# Ultravolt_Board.net
KiCad netlist of a schematic drawn in EAGLE
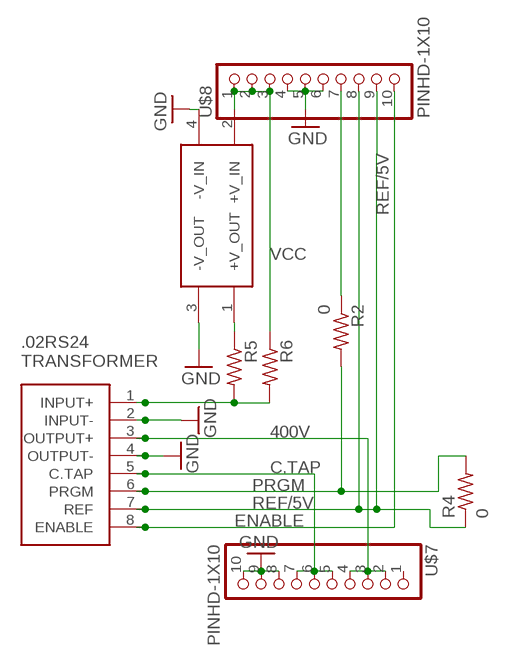
[diagram p0: schematic, sheet 1]

(export (version "E")
  (design (tool "Eeschema 10.0.6"))
  (components
    (comp (ref "$ZX2")
      (value "LUCAS-LIBRARY_12_DC-24_DC")
      (footprint "eagle-import:LUCAS-LIBRARY_12_DC-24_DC")
      (libsource (lib "eagle-import") (part "LUCAS-LIBRARY_12_DC-24_DC"))
    )
    (comp (ref "R2")
      (value "0")
      (footprint "eagle-import:M1206")
      (fields (field (name "SPICEPREFIX") "R"))
      (libsource (lib "eagle-import") (part "R-US_M1206"))
    )
    (comp (ref "R4")
      (value "0")
      (footprint "eagle-import:M1206")
      (fields (field (name "SPICEPREFIX") "R"))
      (libsource (lib "eagle-import") (part "R-US_M1206"))
    )
    (comp (ref "R5")
      (value "ADAFRUIT_R-US_M0805")
      (footprint "eagle-import:ADAFRUIT_M0805")
      (libsource (lib "eagle-import") (part "ADAFRUIT_R-US_M0805"))
    )
    (comp (ref "R6")
      (value "ADAFRUIT_R-US_M0805")
      (footprint "eagle-import:ADAFRUIT_M0805")
      (libsource (lib "eagle-import") (part "ADAFRUIT_R-US_M0805"))
    )
    (comp (ref "U$1")
      (value "ULTRAVOLT_DAUGHTERBOARD_BAT-BOARD-REV-2.0_LUCAS-LIBRARY_.2RS24_TRANSFORMER")
      (footprint "eagle-import:ULTRAVOLT_DAUGHTERBOARD_BAT-BOARD-REV-2.0_LUCAS-LIBRARY_0.2RS24_TRANSFORMER")
      (libsource (lib "eagle-import") (part "ULTRAVOLT_DAUGHTERBOARD_BAT-BOARD-REV-2.0_LUCAS-LIBRARY_.2RS24_TRANSFORMER"))
    )
    (comp (ref "U$7")
      (value "PINHD-1X10")
      (footprint "eagle-import:1X10-BIG")
      (libsource (lib "eagle-import") (part "PINHD-1X10"))
    )
    (comp (ref "U$8")
      (value "PINHD-1X10")
      (footprint "eagle-import:1X10-BIG")
      (libsource (lib "eagle-import") (part "PINHD-1X10"))
    )
  )
  (nets
    (net (code "1") (name "400V") (class "Default")
      (node (ref "U$1") (pin "3") (pinfunction "OUTPUT+_3") (pintype "bidirectional"))
      (node (ref "U$7") (pin "2") (pinfunction "2_2") (pintype "passive"))
      (node (ref "U$7") (pin "3") (pinfunction "3_3") (pintype "passive"))
      (node (ref "U$7") (pin "4") (pinfunction "4_4") (pintype "passive"))
    )
    (net (code "2") (name "C.TAP") (class "Default")
      (node (ref "U$1") (pin "5") (pinfunction "C.TAP_5") (pintype "bidirectional"))
      (node (ref "U$7") (pin "5") (pinfunction "5_5") (pintype "passive"))
      (node (ref "U$7") (pin "6") (pinfunction "6_6") (pintype "passive"))
      (node (ref "U$7") (pin "7") (pinfunction "7_7") (pintype "passive"))
    )
    (net (code "3") (name "ENABLE") (class "Default")
      (node (ref "U$1") (pin "8") (pinfunction "ENABLE_8") (pintype "bidirectional"))
      (node (ref "U$8") (pin "10") (pinfunction "10_10") (pintype "passive"))
    )
    (net (code "4") (name "GND") (class "Default")
      (node (ref "$ZX2") (pin "3") (pinfunction "-V_OUT_3") (pintype "bidirectional"))
      (node (ref "$ZX2") (pin "4") (pinfunction "-V_IN_4") (pintype "bidirectional"))
      (node (ref "U$1") (pin "2") (pinfunction "INPUT-_2") (pintype "bidirectional"))
      (node (ref "U$1") (pin "4") (pinfunction "OUTPUT-_4") (pintype "bidirectional"))
      (node (ref "U$7") (pin "10") (pinfunction "10_10") (pintype "passive"))
      (node (ref "U$7") (pin "8") (pinfunction "8_8") (pintype "passive"))
      (node (ref "U$7") (pin "9") (pinfunction "9_9") (pintype "passive"))
      (node (ref "U$8") (pin "4") (pinfunction "4_4") (pintype "passive"))
      (node (ref "U$8") (pin "5") (pinfunction "5_5") (pintype "passive"))
      (node (ref "U$8") (pin "6") (pinfunction "6_6") (pintype "passive"))
    )
    (net (code "5") (name "Net-($ZX2-+V_OUT)") (class "Default")
      (node (ref "$ZX2") (pin "1") (pinfunction "+V_OUT_1") (pintype "bidirectional"))
      (node (ref "R5") (pin "1") (pinfunction "1_1") (pintype "passive"))
    )
    (net (code "6") (name "Net-(R2-Pad1)") (class "Default")
      (node (ref "R2") (pin "1") (pinfunction "1_1") (pintype "passive"))
      (node (ref "U$8") (pin "7") (pinfunction "7_7") (pintype "passive"))
    )
    (net (code "7") (name "Net-(U$1-INPUT+)") (class "Default")
      (node (ref "R5") (pin "2") (pinfunction "2_2") (pintype "passive"))
      (node (ref "R6") (pin "2") (pinfunction "2_2") (pintype "passive"))
      (node (ref "U$1") (pin "1") (pinfunction "INPUT+_1") (pintype "bidirectional"))
    )
    (net (code "8") (name "PRGM") (class "Default")
      (node (ref "R2") (pin "2") (pinfunction "2_2") (pintype "passive"))
      (node (ref "R4") (pin "2") (pinfunction "2_2") (pintype "passive"))
      (node (ref "U$1") (pin "6") (pinfunction "PRGM_6") (pintype "bidirectional"))
    )
    (net (code "9") (name "REF{slash}5V") (class "Default")
      (node (ref "R4") (pin "1") (pinfunction "1_1") (pintype "passive"))
      (node (ref "U$1") (pin "7") (pinfunction "REF_7") (pintype "bidirectional"))
      (node (ref "U$8") (pin "8") (pinfunction "8_8") (pintype "passive"))
      (node (ref "U$8") (pin "9") (pinfunction "9_9") (pintype "passive"))
    )
    (net (code "10") (name "VCC") (class "Default")
      (node (ref "$ZX2") (pin "2") (pinfunction "+V_IN_2") (pintype "bidirectional"))
      (node (ref "R6") (pin "1") (pinfunction "1_1") (pintype "passive"))
      (node (ref "U$8") (pin "1") (pinfunction "1_1") (pintype "passive"))
      (node (ref "U$8") (pin "2") (pinfunction "2_2") (pintype "passive"))
      (node (ref "U$8") (pin "3") (pinfunction "3_3") (pintype "passive"))
    )
    (net (code "11") (name "unconnected-(U$7-Pad1)") (class "Default")
      (node (ref "U$7") (pin "1") (pinfunction "1_1") (pintype "passive"))
    )
  )
)
